# PowerSupply2.net
KiCad netlist of a schematic drawn in Altium Designer
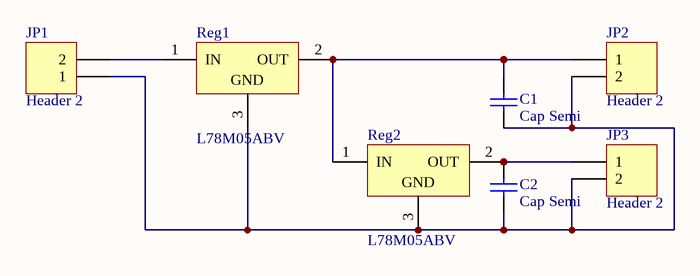
[diagram p0: PowerSupply2.SCHDOC]

(export (version "E")
  (design (tool "Eeschema 10.0.6"))
  (components
    (comp (ref "C1")
      (value "Cap Semi")
      (footprint "CC3216-1206")
      (description "Capacitor (Semiconductor SIM Model)")
      (fields (field (name "PUBLISHER") "Altium Limited"))
      (libsource (lib "Miscellaneous Devices") (part "Cap Semi"))
    )
    (comp (ref "C2")
      (value "Cap Semi")
      (footprint "CC3216-1206")
      (description "Capacitor (Semiconductor SIM Model)")
      (fields (field (name "PUBLISHER") "Altium Limited"))
      (libsource (lib "Miscellaneous Devices") (part "Cap Semi"))
    )
    (comp (ref "JP1")
      (value "Header 2")
      (footprint "HDR1X2")
      (description "Header, 2-Pin")
      (fields (field (name "PUBLISHER") "Altium Limited"))
      (libsource (lib "") (part "Header 2_1"))
    )
    (comp (ref "JP2")
      (value "Header 2")
      (footprint "HDR1X2")
      (description "Header, 2-Pin")
      (fields (field (name "PUBLISHER") "Altium Limited"))
      (libsource (lib "Miscellaneous Connectors") (part "Header 2"))
    )
    (comp (ref "JP3")
      (value "Header 2")
      (footprint "HDR1X2")
      (description "Header, 2-Pin")
      (fields (field (name "PUBLISHER") "Altium Limited"))
      (libsource (lib "Miscellaneous Connectors") (part "Header 2"))
    )
    (comp (ref "Reg1")
      (value "L78M05ABV")
      (footprint "TO220V")
      (description "Precision 500mA Regulator")
      (fields (field (name "PUBLISHER") "Altium Limited"))
      (libsource (lib "ST Power Mgt Voltage Regulator") (part "L78M05ABV"))
    )
    (comp (ref "Reg2")
      (value "L78M05ABV")
      (footprint "TO220V")
      (description "Precision 500mA Regulator")
      (fields (field (name "PUBLISHER") "Altium Limited"))
      (libsource (lib "ST Power Mgt Voltage Regulator") (part "L78M05ABV"))
    )
  )
  (nets
    (net (code "1") (name "Net-(Reg1-GND)") (class "Default")
      (node (ref "C1") (pin "1") (pinfunction "1_1") (pintype "passive"))
      (node (ref "C2") (pin "1") (pinfunction "1_1") (pintype "passive"))
      (node (ref "JP1") (pin "1") (pinfunction "1_1") (pintype "passive"))
      (node (ref "JP2") (pin "2") (pinfunction "2_2") (pintype "passive"))
      (node (ref "JP3") (pin "2") (pinfunction "2_2") (pintype "passive"))
      (node (ref "Reg1") (pin "3") (pinfunction "GND_3") (pintype "power_in"))
      (node (ref "Reg2") (pin "3") (pinfunction "GND_3") (pintype "power_in"))
    )
    (net (code "2") (name "Net-(Reg1-IN)") (class "Default")
      (node (ref "JP1") (pin "2") (pinfunction "2_2") (pintype "passive"))
      (node (ref "Reg1") (pin "1") (pinfunction "IN_1") (pintype "power_in"))
    )
    (net (code "3") (name "Net-(Reg1-OUT)") (class "Default")
      (node (ref "C1") (pin "2") (pinfunction "2_2") (pintype "passive"))
      (node (ref "JP2") (pin "1") (pinfunction "1_1") (pintype "passive"))
      (node (ref "Reg1") (pin "2") (pinfunction "OUT_2") (pintype "power_in"))
      (node (ref "Reg2") (pin "1") (pinfunction "IN_1") (pintype "power_in"))
    )
    (net (code "4") (name "Net-(Reg2-OUT)") (class "Default")
      (node (ref "C2") (pin "2") (pinfunction "2_2") (pintype "passive"))
      (node (ref "JP3") (pin "1") (pinfunction "1_1") (pintype "passive"))
      (node (ref "Reg2") (pin "2") (pinfunction "OUT_2") (pintype "power_in"))
    )
  )
)
